# Controller.net
KiCad netlist of a schematic drawn in Altium Designer
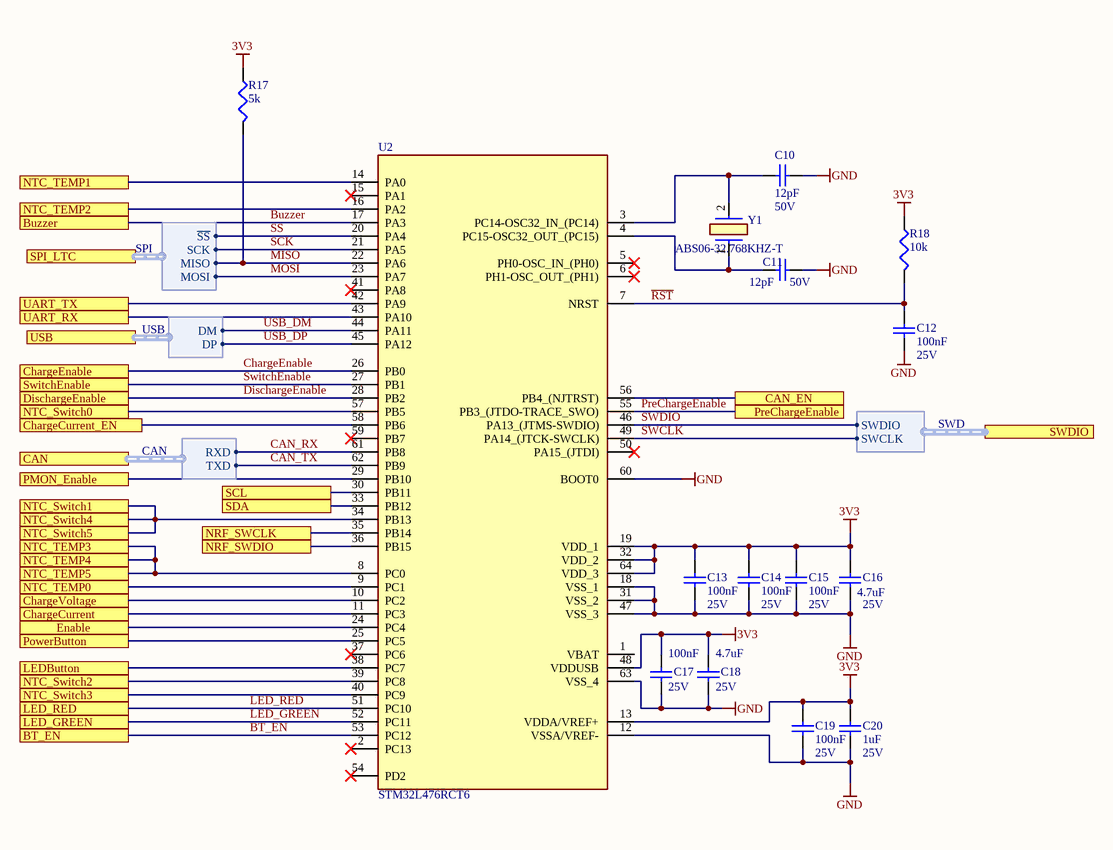
[diagram p0: Controller.SchDoc]

(export (version "E")
  (design (tool "Eeschema 10.0.6"))
  (components
    (comp (ref "C10")
      (value "12pF")
      (footprint "VESC_BMS:C0402")
      (description "Capacitor, 18pF, 50V, NP0")
      (fields (field (name "VOLTAGE RATING") "50V"))
      (libsource (lib "AR_Capacitors_Ceramic") (part "18pF/0402/CER/50V"))
    )
    (comp (ref "C11")
      (value "12pF")
      (footprint "VESC_BMS:C0402")
      (description "Capacitor, 18pF, 50V, NP0")
      (fields (field (name "VOLTAGE RATING") "50V"))
      (libsource (lib "AR_Capacitors_Ceramic") (part "18pF/0402/CER/50V"))
    )
    (comp (ref "C12")
      (value "100nF")
      (footprint "VESC_BMS:C0402")
      (description "Capacitor, 100nF, 25V, X7R")
      (fields (field (name "VOLTAGE RATING") "25V"))
      (libsource (lib "AR_Capacitors_Ceramic") (part "100nF/0402/CER/25V"))
    )
    (comp (ref "C13")
      (value "100nF")
      (footprint "VESC_BMS:C0402")
      (description "Capacitor, 100nF, 25V, X7R")
      (fields (field (name "VOLTAGE RATING") "25V"))
      (libsource (lib "AR_Capacitors_Ceramic") (part "100nF/0402/CER/25V"))
    )
    (comp (ref "C14")
      (value "100nF")
      (footprint "VESC_BMS:C0402")
      (description "Capacitor, 100nF, 25V, X7R")
      (fields (field (name "VOLTAGE RATING") "25V"))
      (libsource (lib "AR_Capacitors_Ceramic") (part "100nF/0402/CER/25V"))
    )
    (comp (ref "C15")
      (value "100nF")
      (footprint "VESC_BMS:C0402")
      (description "Capacitor, 100nF, 25V, X7R")
      (fields (field (name "VOLTAGE RATING") "25V"))
      (libsource (lib "AR_Capacitors_Ceramic") (part "100nF/0402/CER/25V"))
    )
    (comp (ref "C16")
      (value "4.7uF")
      (footprint "VESC_BMS:C0402")
      (description "Capacitor, 100nF, 25V, X7R")
      (fields (field (name "VOLTAGE RATING") "25V"))
      (libsource (lib "AR_Capacitors_Ceramic") (part "100nF/0402/CER/25V"))
    )
    (comp (ref "C17")
      (value "100nF")
      (footprint "VESC_BMS:C0402")
      (description "Capacitor, 100nF, 25V, X7R")
      (fields (field (name "VOLTAGE RATING") "25V"))
      (libsource (lib "AR_Capacitors_Ceramic") (part "100nF/0402/CER/25V"))
    )
    (comp (ref "C18")
      (value "4.7uF")
      (footprint "VESC_BMS:C0402")
      (description "Capacitor, 100nF, 25V, X7R")
      (fields (field (name "VOLTAGE RATING") "25V"))
      (libsource (lib "AR_Capacitors_Ceramic") (part "100nF/0402/CER/25V"))
    )
    (comp (ref "C19")
      (value "100nF")
      (footprint "VESC_BMS:C0402")
      (description "Capacitor, 100nF, 25V, X7R")
      (fields (field (name "VOLTAGE RATING") "25V"))
      (libsource (lib "AR_Capacitors_Ceramic") (part "100nF/0402/CER/25V"))
    )
    (comp (ref "C20")
      (value "1uF")
      (footprint "VESC_BMS:C0402")
      (description "Capacitor, 100nF, 25V, X7R")
      (fields (field (name "VOLTAGE RATING") "25V"))
      (libsource (lib "AR_Capacitors_Ceramic") (part "100nF/0402/CER/25V"))
    )
    (comp (ref "R17")
      (value "5k")
      (footprint "VESC_BMS:0402")
      (description "Resistor, 10k, 0.1%, 0.0625W, 50V, 100PPM, 0402")
      (libsource (lib "AR_Resistors_SMD") (part "10k/0402/0063W/50V"))
    )
    (comp (ref "R18")
      (value "10k")
      (footprint "VESC_BMS:0402")
      (description "Resistor, 10k, 0.1%, 0.0625W, 50V, 100PPM, 0402")
      (libsource (lib "AR_Resistors_SMD") (part "10k/0402/0063W/50V"))
    )
    (comp (ref "U2")
      (value "STM32L476RCT6")
      (footprint "VESC_BMS:QFP50P1200X1200X160-64N")
      (description "Integrated Circuit")
      (fields (field (name "MOUSER PART NUMBER") "511-STM32L476RCT6"))
      (libsource (lib "DB10005_DieBieMS") (part "STM32L476RCT6"))
    )
    (comp (ref "Y1")
      (value "ABS06-32.768KHZ-T")
      (footprint "VESC_BMS:OSC-SMD_L2.0-W1.2")
      (description "Crystal or Oscillator")
      (fields
        (field (name "MANUFACTURER_PART_NUMBER") "ABS05-32.768KHZ-9-T")
        (field (name "MOUSER PART NUMBER") "815-ABS05-32.768K9T")
      )
      (libsource (lib "VESC_BMS") (part "ABS06-32.768KHZ-T"))
    )
  )
  (nets
    (net (code "5") (name "/BT_EN") (class "Default")
      (node (ref "U2") (pin "53") (pinfunction "PC12_53") (pintype "passive"))
    )
    (net (code "6") (name "/Buzzer") (class "Default")
      (node (ref "U2") (pin "17") (pinfunction "PA3_17") (pintype "passive"))
    )
    (net (code "7") (name "/CAN_EN") (class "Default")
      (node (ref "U2") (pin "56") (pinfunction "PB4_(NJTRST)_56") (pintype "passive"))
    )
    (net (code "8") (name "/CAN_RX") (class "Default")
      (node (ref "U2") (pin "61") (pinfunction "PB8_61") (pintype "passive"))
    )
    (net (code "9") (name "/CAN_TX") (class "Default")
      (node (ref "U2") (pin "62") (pinfunction "PB9_62") (pintype "passive"))
    )
    (net (code "10") (name "/ChargeCurrent") (class "Default")
      (node (ref "U2") (pin "11") (pinfunction "PC3_11") (pintype "passive"))
    )
    (net (code "11") (name "/ChargeCurrent_EN") (class "Default")
      (node (ref "U2") (pin "58") (pinfunction "PB6_58") (pintype "passive"))
    )
    (net (code "12") (name "/ChargeEnable") (class "Default")
      (node (ref "U2") (pin "26") (pinfunction "PB0_26") (pintype "passive"))
    )
    (net (code "13") (name "/ChargeVoltage") (class "Default")
      (node (ref "U2") (pin "10") (pinfunction "PC2_10") (pintype "passive"))
    )
    (net (code "14") (name "/DischargeEnable") (class "Default")
      (node (ref "U2") (pin "28") (pinfunction "PB2_28") (pintype "passive"))
    )
    (net (code "15") (name "/Enable") (class "Default")
      (node (ref "U2") (pin "24") (pinfunction "PC4_24") (pintype "passive"))
    )
    (net (code "16") (name "/LEDButton") (class "Default")
      (node (ref "U2") (pin "38") (pinfunction "PC7_38") (pintype "passive"))
    )
    (net (code "17") (name "/LED_GREEN") (class "Default")
      (node (ref "U2") (pin "52") (pinfunction "PC11_52") (pintype "passive"))
    )
    (net (code "18") (name "/LED_RED") (class "Default")
      (node (ref "U2") (pin "51") (pinfunction "PC10_51") (pintype "passive"))
    )
    (net (code "19") (name "/MISO") (class "Default")
      (node (ref "R17") (pin "1") (pinfunction "1_1") (pintype "passive"))
      (node (ref "U2") (pin "22") (pinfunction "PA6_22") (pintype "passive"))
    )
    (net (code "20") (name "/MOSI") (class "Default")
      (node (ref "U2") (pin "23") (pinfunction "PA7_23") (pintype "passive"))
    )
    (net (code "21") (name "/NRF_SWCLK") (class "Default")
      (node (ref "U2") (pin "35") (pinfunction "PB14_35") (pintype "passive"))
    )
    (net (code "22") (name "/NRF_SWDIO") (class "Default")
      (node (ref "U2") (pin "36") (pinfunction "PB15_36") (pintype "passive"))
    )
    (net (code "23") (name "/NTC_Switch0") (class "Default")
      (node (ref "U2") (pin "57") (pinfunction "PB5_57") (pintype "passive"))
    )
    (net (code "24") (name "/NTC_Switch1") (class "Default")
      (node (ref "U2") (pin "34") (pinfunction "PB13_34") (pintype "passive"))
    )
    (net (code "25") (name "/NTC_Switch2") (class "Default")
      (node (ref "U2") (pin "39") (pinfunction "PC8_39") (pintype "passive"))
    )
    (net (code "26") (name "/NTC_Switch3") (class "Default")
      (node (ref "U2") (pin "40") (pinfunction "PC9_40") (pintype "passive"))
    )
    (net (code "27") (name "/NTC_TEMP0") (class "Default")
      (node (ref "U2") (pin "9") (pinfunction "PC1_9") (pintype "passive"))
    )
    (net (code "28") (name "/NTC_TEMP1") (class "Default")
      (node (ref "U2") (pin "14") (pinfunction "PA0_14") (pintype "passive"))
    )
    (net (code "29") (name "/NTC_TEMP2") (class "Default")
      (node (ref "U2") (pin "16") (pinfunction "PA2_16") (pintype "passive"))
    )
    (net (code "30") (name "/NTC_TEMP3") (class "Default")
      (node (ref "U2") (pin "8") (pinfunction "PC0_8") (pintype "passive"))
    )
    (net (code "31") (name "/PMON_Enable") (class "Default")
      (node (ref "U2") (pin "29") (pinfunction "PB10_29") (pintype "passive"))
    )
    (net (code "32") (name "/PowerButton") (class "Default")
      (node (ref "U2") (pin "25") (pinfunction "PC5_25") (pintype "passive"))
    )
    (net (code "33") (name "/PreChargeEnable") (class "Default")
      (node (ref "U2") (pin "55") (pinfunction "PB3_(JTDO-TRACE_SWO)_55") (pintype "passive"))
    )
    (net (code "34") (name "/SCK") (class "Default")
      (node (ref "U2") (pin "21") (pinfunction "PA5_21") (pintype "passive"))
    )
    (net (code "35") (name "/SCL") (class "Default")
      (node (ref "U2") (pin "30") (pinfunction "PB11_30") (pintype "passive"))
    )
    (net (code "36") (name "/SDA") (class "Default")
      (node (ref "U2") (pin "33") (pinfunction "PB12_33") (pintype "passive"))
    )
    (net (code "37") (name "/SWCLK") (class "Default")
      (node (ref "U2") (pin "49") (pinfunction "PA14_(JTCK-SWCLK)_49") (pintype "passive"))
    )
    (net (code "38") (name "/SWDIO") (class "Default")
      (node (ref "U2") (pin "46") (pinfunction "PA13_(JTMS-SWDIO)_46") (pintype "passive"))
    )
    (net (code "39") (name "/SwitchEnable") (class "Default")
      (node (ref "U2") (pin "27") (pinfunction "PB1_27") (pintype "passive"))
    )
    (net (code "40") (name "/UART_RX") (class "Default")
      (node (ref "U2") (pin "43") (pinfunction "PA10_43") (pintype "passive"))
    )
    (net (code "41") (name "/UART_TX") (class "Default")
      (node (ref "U2") (pin "42") (pinfunction "PA9_42") (pintype "passive"))
    )
    (net (code "42") (name "/USB_DM") (class "Default")
      (node (ref "U2") (pin "44") (pinfunction "PA11_44") (pintype "passive"))
    )
    (net (code "43") (name "/USB_DP") (class "Default")
      (node (ref "U2") (pin "45") (pinfunction "PA12_45") (pintype "passive"))
    )
    (net (code "48") (name "/~{RST}") (class "Default")
      (node (ref "C12") (pin "2") (pinfunction "2_2") (pintype "passive"))
      (node (ref "R18") (pin "1") (pinfunction "1_1") (pintype "passive"))
      (node (ref "U2") (pin "7") (pinfunction "NRST_7") (pintype "passive"))
    )
    (net (code "49") (name "/~{SS}") (class "Default")
      (node (ref "U2") (pin "20") (pinfunction "PA4_20") (pintype "passive"))
    )
    (net (code "50") (name "3V3") (class "Default")
      (node (ref "C13") (pin "2") (pinfunction "2_2") (pintype "passive"))
      (node (ref "C14") (pin "2") (pinfunction "2_2") (pintype "passive"))
      (node (ref "C15") (pin "2") (pinfunction "2_2") (pintype "passive"))
      (node (ref "C16") (pin "2") (pinfunction "2_2") (pintype "passive"))
      (node (ref "C17") (pin "2") (pinfunction "2_2") (pintype "passive"))
      (node (ref "C18") (pin "2") (pinfunction "2_2") (pintype "passive"))
      (node (ref "C19") (pin "2") (pinfunction "2_2") (pintype "passive"))
      (node (ref "C20") (pin "2") (pinfunction "2_2") (pintype "passive"))
      (node (ref "R17") (pin "2") (pinfunction "2_2") (pintype "passive"))
      (node (ref "R18") (pin "2") (pinfunction "2_2") (pintype "passive"))
      (node (ref "U2") (pin "13") (pinfunction "VDDA/VREF+_13") (pintype "passive"))
      (node (ref "U2") (pin "19") (pinfunction "VDD_1_19") (pintype "passive"))
      (node (ref "U2") (pin "32") (pinfunction "VDD_2_32") (pintype "passive"))
      (node (ref "U2") (pin "48") (pinfunction "VDDUSB_48") (pintype "passive"))
      (node (ref "U2") (pin "64") (pinfunction "VDD_3_64") (pintype "passive"))
    )
    (net (code "51") (name "GND") (class "Default")
      (node (ref "C10") (pin "1") (pinfunction "1_1") (pintype "passive"))
      (node (ref "C11") (pin "1") (pinfunction "1_1") (pintype "passive"))
      (node (ref "C12") (pin "1") (pinfunction "1_1") (pintype "passive"))
      (node (ref "C13") (pin "1") (pinfunction "1_1") (pintype "passive"))
      (node (ref "C14") (pin "1") (pinfunction "1_1") (pintype "passive"))
      (node (ref "C15") (pin "1") (pinfunction "1_1") (pintype "passive"))
      (node (ref "C16") (pin "1") (pinfunction "1_1") (pintype "passive"))
      (node (ref "C17") (pin "1") (pinfunction "1_1") (pintype "passive"))
      (node (ref "C18") (pin "1") (pinfunction "1_1") (pintype "passive"))
      (node (ref "C19") (pin "1") (pinfunction "1_1") (pintype "passive"))
      (node (ref "C20") (pin "1") (pinfunction "1_1") (pintype "passive"))
      (node (ref "U2") (pin "12") (pinfunction "VSSA/VREF-_12") (pintype "passive"))
      (node (ref "U2") (pin "18") (pinfunction "VSS_1_18") (pintype "passive"))
      (node (ref "U2") (pin "31") (pinfunction "VSS_2_31") (pintype "passive"))
      (node (ref "U2") (pin "47") (pinfunction "VSS_3_47") (pintype "passive"))
      (node (ref "U2") (pin "60") (pinfunction "BOOT0_60") (pintype "passive"))
      (node (ref "U2") (pin "63") (pinfunction "VSS_4_63") (pintype "passive"))
    )
    (net (code "52") (name "Net-(U2-PC14-OSC32_IN_(PC14))") (class "Default")
      (node (ref "C10") (pin "2") (pinfunction "2_2") (pintype "passive"))
      (node (ref "U2") (pin "3") (pinfunction "PC14-OSC32_IN_(PC14)_3") (pintype "passive"))
      (node (ref "Y1") (pin "2") (pinfunction "2_2") (pintype "passive"))
    )
    (net (code "53") (name "Net-(U2-PC15-OSC32_OUT_(PC15))") (class "Default")
      (node (ref "C11") (pin "2") (pinfunction "2_2") (pintype "passive"))
      (node (ref "U2") (pin "4") (pinfunction "PC15-OSC32_OUT_(PC15)_4") (pintype "passive"))
      (node (ref "Y1") (pin "1") (pinfunction "1_1") (pintype "passive"))
    )
    (net (code "54") (name "unconnected-(U2-PA1-Pad15)") (class "Default")
      (node (ref "U2") (pin "15") (pinfunction "PA1_15") (pintype "passive+no_connect"))
    )
    (net (code "55") (name "unconnected-(U2-PA8-Pad41)") (class "Default")
      (node (ref "U2") (pin "41") (pinfunction "PA8_41") (pintype "passive+no_connect"))
    )
    (net (code "56") (name "unconnected-(U2-PA15_(JTDI)-Pad50)") (class "Default")
      (node (ref "U2") (pin "50") (pinfunction "PA15_(JTDI)_50") (pintype "passive+no_connect"))
    )
    (net (code "57") (name "unconnected-(U2-PB7-Pad59)") (class "Default")
      (node (ref "U2") (pin "59") (pinfunction "PB7_59") (pintype "passive+no_connect"))
    )
    (net (code "58") (name "unconnected-(U2-PC6-Pad37)") (class "Default")
      (node (ref "U2") (pin "37") (pinfunction "PC6_37") (pintype "passive+no_connect"))
    )
    (net (code "59") (name "unconnected-(U2-PC13-Pad2)") (class "Default")
      (node (ref "U2") (pin "2") (pinfunction "PC13_2") (pintype "passive+no_connect"))
    )
    (net (code "60") (name "unconnected-(U2-PD2-Pad54)") (class "Default")
      (node (ref "U2") (pin "54") (pinfunction "PD2_54") (pintype "passive+no_connect"))
    )
    (net (code "61") (name "unconnected-(U2-PH0-OSC_IN_(PH0)-Pad5)") (class "Default")
      (node (ref "U2") (pin "5") (pinfunction "PH0-OSC_IN_(PH0)_5") (pintype "passive+no_connect"))
    )
    (net (code "62") (name "unconnected-(U2-PH1-OSC_OUT_(PH1)-Pad6)") (class "Default")
      (node (ref "U2") (pin "6") (pinfunction "PH1-OSC_OUT_(PH1)_6") (pintype "passive+no_connect"))
    )
    (net (code "63") (name "unconnected-(U2-VBAT-Pad1)") (class "Default")
      (node (ref "U2") (pin "1") (pinfunction "VBAT_1") (pintype "passive"))
    )
  )
)
